# Audio_Amplifier_Rev_C2.net
KiCad netlist of a schematic drawn in EAGLE
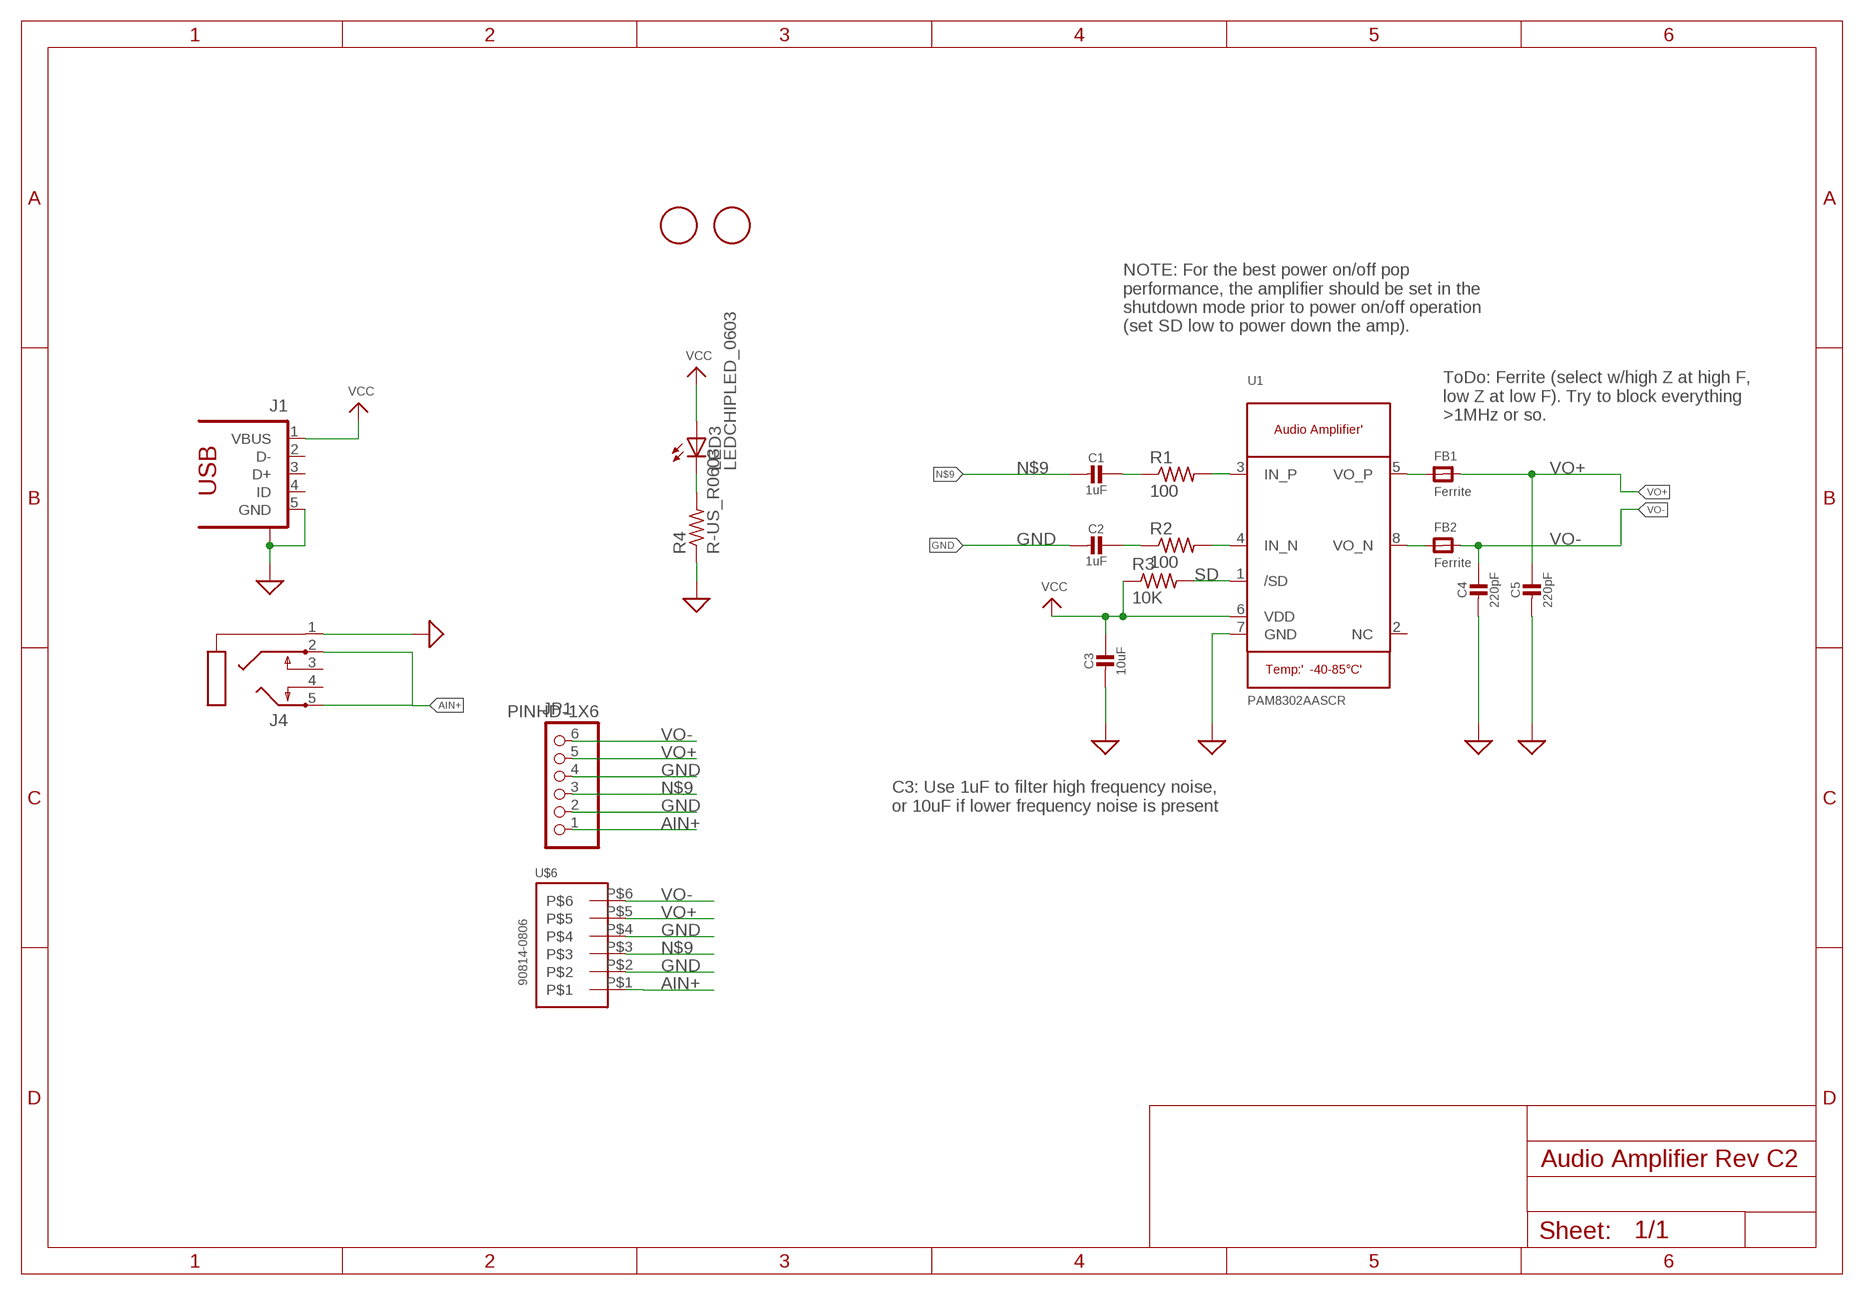
[diagram p0: schematic, sheet 1]

(export (version "E")
  (design (tool "Eeschema 10.0.6"))
  (components
    (comp (ref "C1")
      (value "1uF")
      (footprint "eagle-import:0805-NO")
      (libsource (lib "eagle-import") (part "CAP_CERAMIC0805-NOOUTLINE"))
    )
    (comp (ref "C2")
      (value "1uF")
      (footprint "eagle-import:0805-NO")
      (libsource (lib "eagle-import") (part "CAP_CERAMIC0805-NOOUTLINE"))
    )
    (comp (ref "C3")
      (value "10uF")
      (footprint "eagle-import:0805-NO")
      (libsource (lib "eagle-import") (part "CAP_CERAMIC0805-NOOUTLINE"))
    )
    (comp (ref "C4")
      (value "220pF")
      (footprint "eagle-import:0805-NO")
      (libsource (lib "eagle-import") (part "CAP_CERAMIC0805-NOOUTLINE"))
    )
    (comp (ref "C5")
      (value "220pF")
      (footprint "eagle-import:0805-NO")
      (libsource (lib "eagle-import") (part "CAP_CERAMIC0805-NOOUTLINE"))
    )
    (comp (ref "FB1")
      (value "Ferrite")
      (footprint "eagle-import:_0805")
      (libsource (lib "eagle-import") (part "FERRITE_0805"))
    )
    (comp (ref "FB2")
      (value "Ferrite")
      (footprint "eagle-import:_0805")
      (libsource (lib "eagle-import") (part "FERRITE_0805"))
    )
    (comp (ref "J1")
      (value "1981584-1")
      (footprint "eagle-import:1981584-1")
      (libsource (lib "eagle-import") (part "1981584-1"))
    )
    (comp (ref "J4")
      (value "STEREOJACK")
      (footprint "eagle-import:STX3100")
      (libsource (lib "eagle-import") (part "STEREOJACK"))
    )
    (comp (ref "JP1")
      (value "PINHD-1X6")
      (footprint "eagle-import:1X06")
      (libsource (lib "eagle-import") (part "PINHD-1X6"))
    )
    (comp (ref "LED3")
      (value "LEDCHIPLED_0603")
      (footprint "eagle-import:CHIPLED_0603")
      (libsource (lib "eagle-import") (part "LEDCHIPLED_0603"))
    )
    (comp (ref "R1")
      (value "100")
      (footprint "eagle-import:R0603")
      (libsource (lib "eagle-import") (part "R-US_R0603"))
    )
    (comp (ref "R2")
      (value "100")
      (footprint "eagle-import:R0603")
      (libsource (lib "eagle-import") (part "R-US_R0603"))
    )
    (comp (ref "R3")
      (value "10K")
      (footprint "eagle-import:R0603")
      (libsource (lib "eagle-import") (part "R-US_R0603"))
    )
    (comp (ref "R4")
      (value "R-US_R0603")
      (footprint "eagle-import:R0603")
      (libsource (lib "eagle-import") (part "R-US_R0603"))
    )
    (comp (ref "U$3")
      (value "FIDUCIAL")
      (footprint "eagle-import:FIDUCIAL_1MM")
      (libsource (lib "eagle-import") (part "FIDUCIAL"))
    )
    (comp (ref "U$4")
      (value "FIDUCIAL")
      (footprint "eagle-import:FIDUCIAL_1MM")
      (libsource (lib "eagle-import") (part "FIDUCIAL"))
    )
    (comp (ref "U$6")
      (value "90814-0806")
      (footprint "eagle-import:90814-0806")
      (libsource (lib "eagle-import") (part "90814-0806"))
    )
    (comp (ref "U1")
      (value "PAM8302AASCR")
      (footprint "eagle-import:MSOP8_0.65MM")
      (libsource (lib "eagle-import") (part "AUDIOAMP_PAM8302A"))
    )
  )
  (nets
    (net (code "1") (name "/SD") (class "Default")
      (node (ref "R3") (pin "2") (pinfunction "2_2") (pintype "passive"))
      (node (ref "U1") (pin "1") (pinfunction "/SD_1") (pintype "input"))
    )
    (net (code "2") (name "AIN+") (class "Default")
      (node (ref "J4") (pin "2") (pinfunction "2_2") (pintype "passive"))
      (node (ref "J4") (pin "5") (pinfunction "5_5") (pintype "passive"))
      (node (ref "JP1") (pin "1") (pinfunction "1_1") (pintype "passive"))
      (node (ref "U$6") (pin "P$1") (pinfunction "P$1_P$1") (pintype "bidirectional"))
    )
    (net (code "3") (name "GND") (class "Default")
      (node (ref "C2") (pin "2") (pinfunction "2_2") (pintype "passive"))
      (node (ref "C3") (pin "2") (pinfunction "2_2") (pintype "passive"))
      (node (ref "C4") (pin "2") (pinfunction "2_2") (pintype "passive"))
      (node (ref "C5") (pin "2") (pinfunction "2_2") (pintype "passive"))
      (node (ref "J1") (pin "5") (pinfunction "GND_5") (pintype "passive"))
      (node (ref "J1") (pin "S1") (pinfunction "S1_S1") (pintype "passive"))
      (node (ref "J4") (pin "1") (pinfunction "1_1") (pintype "passive"))
      (node (ref "JP1") (pin "2") (pinfunction "2_2") (pintype "passive"))
      (node (ref "JP1") (pin "4") (pinfunction "4_4") (pintype "passive"))
      (node (ref "R4") (pin "1") (pinfunction "1_1") (pintype "passive"))
      (node (ref "U$6") (pin "P$2") (pinfunction "P$2_P$2") (pintype "bidirectional"))
      (node (ref "U$6") (pin "P$4") (pinfunction "P$4_P$4") (pintype "bidirectional"))
      (node (ref "U1") (pin "7") (pinfunction "GND_7") (pintype "power_in"))
    )
    (net (code "4") (name "N$9") (class "Default")
      (node (ref "C1") (pin "2") (pinfunction "2_2") (pintype "passive"))
      (node (ref "JP1") (pin "3") (pinfunction "3_3") (pintype "passive"))
      (node (ref "U$6") (pin "P$3") (pinfunction "P$3_P$3") (pintype "bidirectional"))
    )
    (net (code "5") (name "Net-(C1-Pad1)") (class "Default")
      (node (ref "C1") (pin "1") (pinfunction "1_1") (pintype "passive"))
      (node (ref "R1") (pin "1") (pinfunction "1_1") (pintype "passive"))
    )
    (net (code "6") (name "Net-(C2-Pad1)") (class "Default")
      (node (ref "C2") (pin "1") (pinfunction "1_1") (pintype "passive"))
      (node (ref "R2") (pin "1") (pinfunction "1_1") (pintype "passive"))
    )
    (net (code "7") (name "Net-(FB1-P$1)") (class "Default")
      (node (ref "FB1") (pin "1") (pinfunction "P$1_1") (pintype "passive"))
      (node (ref "U1") (pin "5") (pinfunction "VO_P_5") (pintype "output"))
    )
    (net (code "8") (name "Net-(FB2-P$1)") (class "Default")
      (node (ref "FB2") (pin "1") (pinfunction "P$1_1") (pintype "passive"))
      (node (ref "U1") (pin "8") (pinfunction "VO_N_8") (pintype "output"))
    )
    (net (code "9") (name "Net-(LED3-PadC)") (class "Default")
      (node (ref "LED3") (pin "C") (pinfunction "C_C") (pintype "passive"))
      (node (ref "R4") (pin "2") (pinfunction "2_2") (pintype "passive"))
    )
    (net (code "10") (name "Net-(U1-IN_N)") (class "Default")
      (node (ref "R2") (pin "2") (pinfunction "2_2") (pintype "passive"))
      (node (ref "U1") (pin "4") (pinfunction "IN_N_4") (pintype "input"))
    )
    (net (code "11") (name "Net-(U1-IN_P)") (class "Default")
      (node (ref "R1") (pin "2") (pinfunction "2_2") (pintype "passive"))
      (node (ref "U1") (pin "3") (pinfunction "IN_P_3") (pintype "input"))
    )
    (net (code "12") (name "VCC") (class "Default")
      (node (ref "C3") (pin "1") (pinfunction "1_1") (pintype "passive"))
      (node (ref "J1") (pin "1") (pinfunction "VBUS_1") (pintype "passive"))
      (node (ref "LED3") (pin "A") (pinfunction "A_A") (pintype "passive"))
      (node (ref "R3") (pin "1") (pinfunction "1_1") (pintype "passive"))
      (node (ref "U1") (pin "6") (pinfunction "VDD_6") (pintype "power_in"))
    )
    (net (code "13") (name "VO+") (class "Default")
      (node (ref "C5") (pin "1") (pinfunction "1_1") (pintype "passive"))
      (node (ref "FB1") (pin "2") (pinfunction "P$2_2") (pintype "passive"))
      (node (ref "JP1") (pin "5") (pinfunction "5_5") (pintype "passive"))
      (node (ref "U$6") (pin "P$5") (pinfunction "P$5_P$5") (pintype "bidirectional"))
    )
    (net (code "14") (name "VO-") (class "Default")
      (node (ref "C4") (pin "1") (pinfunction "1_1") (pintype "passive"))
      (node (ref "FB2") (pin "2") (pinfunction "P$2_2") (pintype "passive"))
      (node (ref "JP1") (pin "6") (pinfunction "6_6") (pintype "passive"))
      (node (ref "U$6") (pin "P$6") (pinfunction "P$6_P$6") (pintype "bidirectional"))
    )
    (net (code "15") (name "unconnected-(J1-D+-Pad3)") (class "Default")
      (node (ref "J1") (pin "3") (pinfunction "D+_3") (pintype "passive"))
    )
    (net (code "16") (name "unconnected-(J1-D--Pad2)") (class "Default")
      (node (ref "J1") (pin "2") (pinfunction "D-_2") (pintype "passive"))
    )
    (net (code "17") (name "unconnected-(J1-ID-Pad4)") (class "Default")
      (node (ref "J1") (pin "4") (pinfunction "ID_4") (pintype "passive"))
    )
    (net (code "18") (name "unconnected-(J4-Pad3)") (class "Default")
      (node (ref "J4") (pin "3") (pinfunction "3_3") (pintype "passive"))
    )
    (net (code "19") (name "unconnected-(J4-Pad4)") (class "Default")
      (node (ref "J4") (pin "4") (pinfunction "4_4") (pintype "passive"))
    )
    (net (code "20") (name "unconnected-(U1-NC-Pad2)") (class "Default")
      (node (ref "U1") (pin "2") (pinfunction "NC_2") (pintype "no_connect"))
    )
  )
)
